# OpenEVSE_PLUS_v5.net
KiCad netlist of a schematic drawn in EAGLE
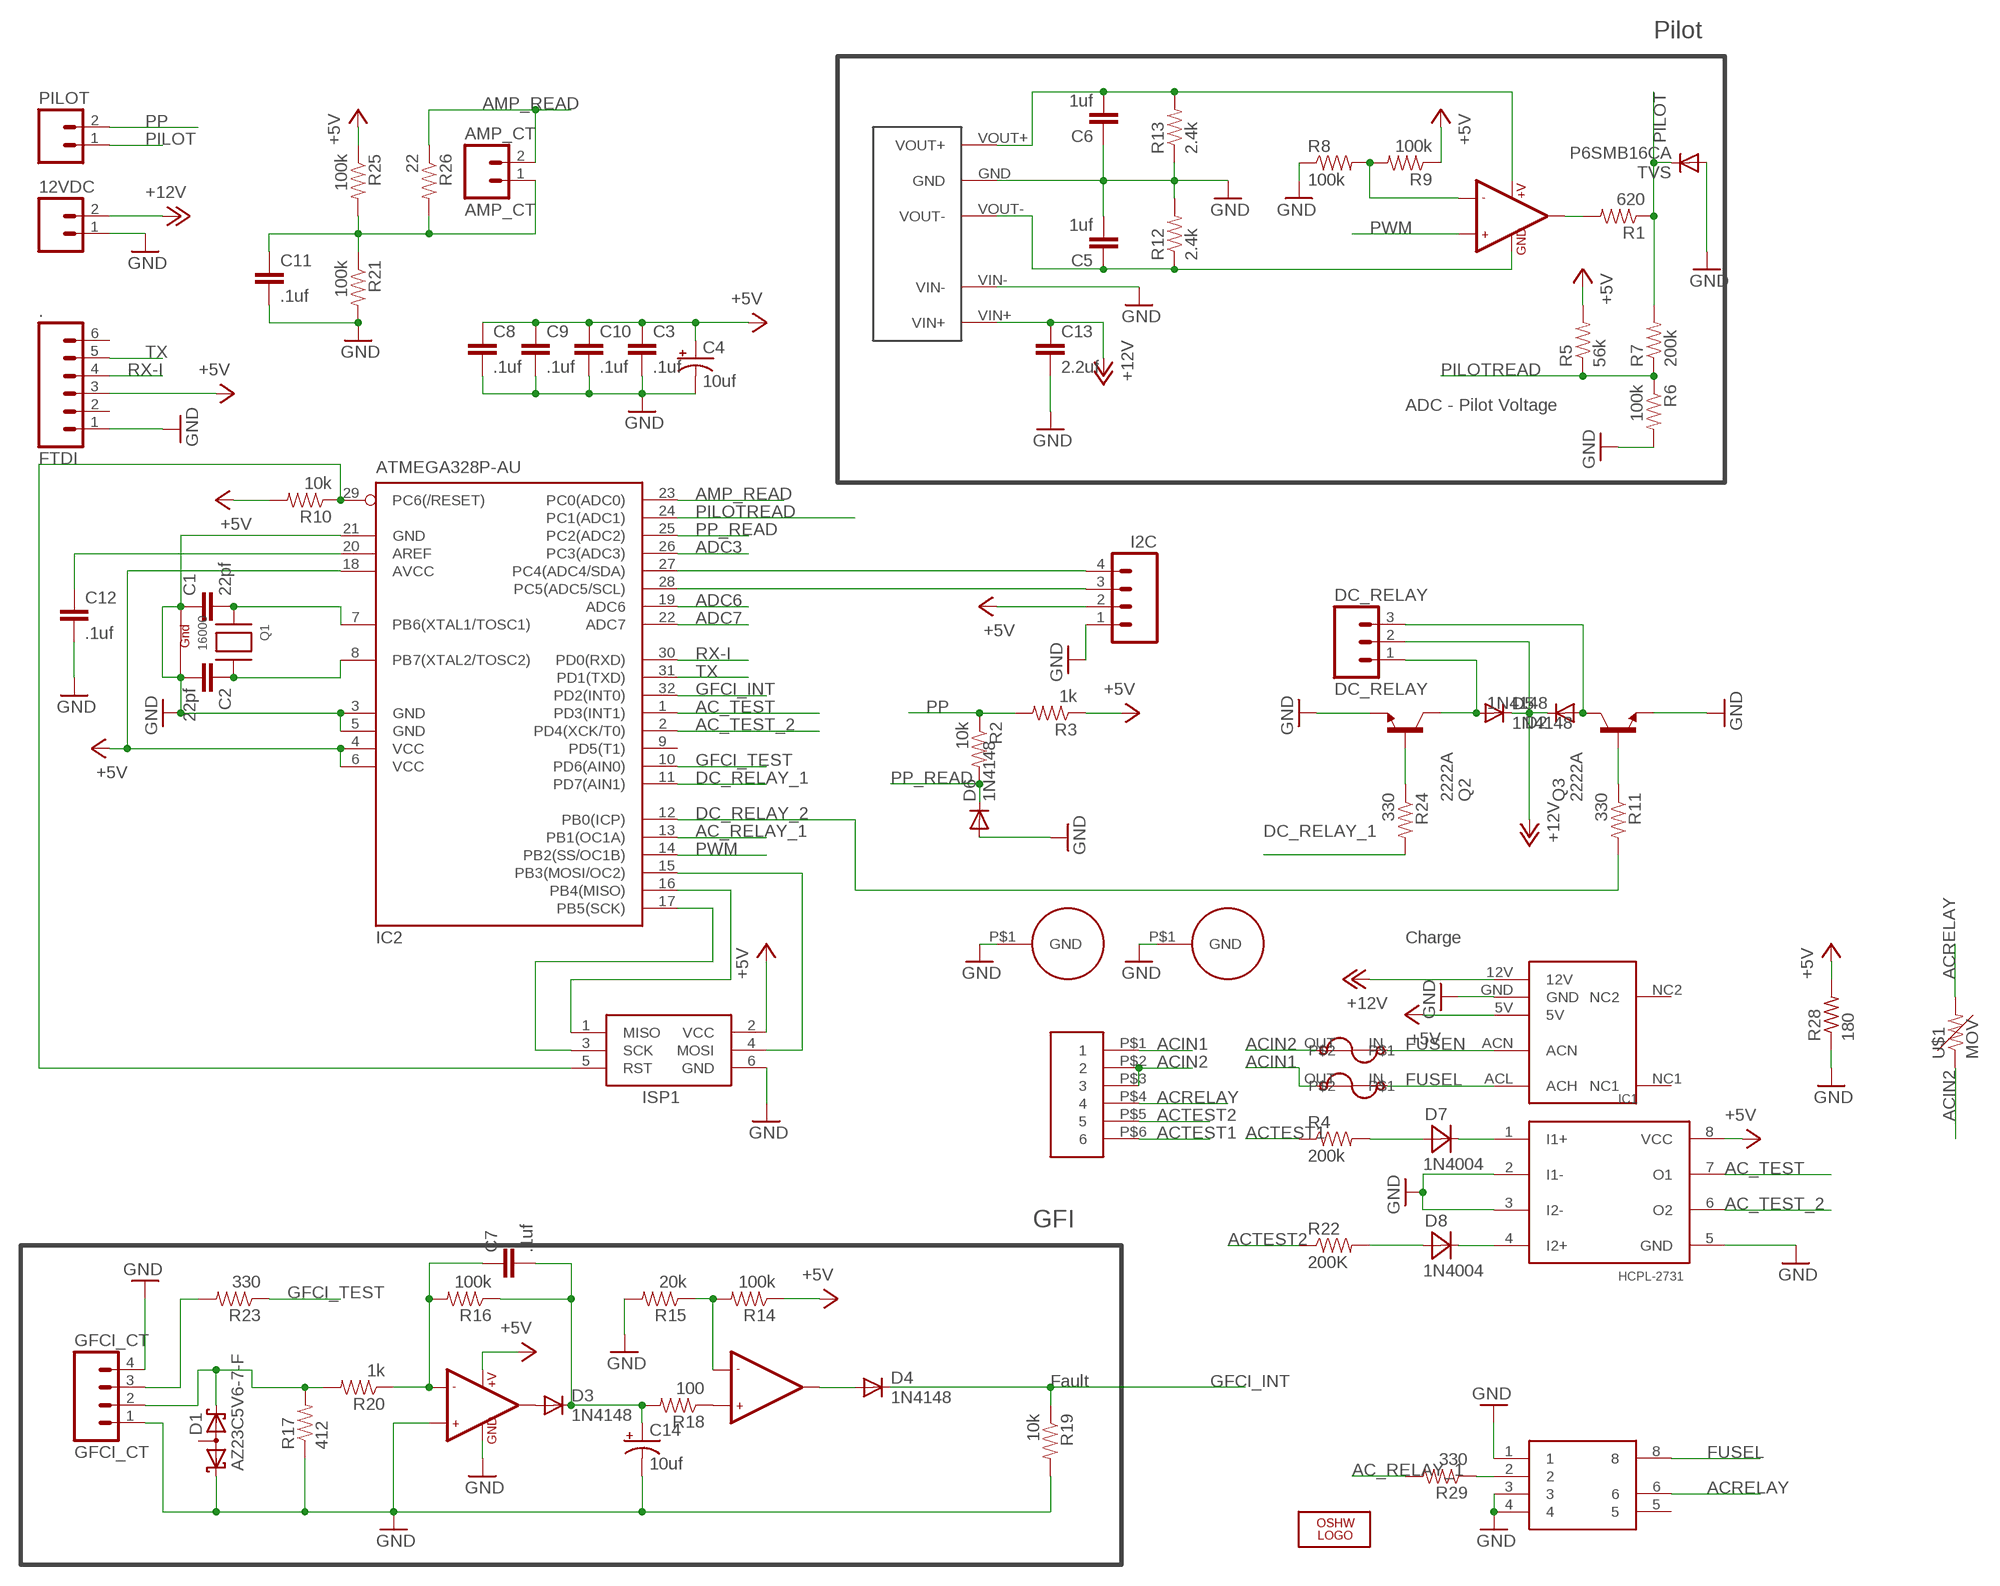
[diagram p0: schematic, sheet 1]

(export (version "E")
  (design (tool "Eeschema 10.0.6"))
  (components
    (comp (ref ".")
      (value "FTDI")
      (footprint "eagle-import:1X06_LOCK")
      (libsource (lib "eagle-import") (part "M06LOCK"))
    )
    (comp (ref "12VDC")
      (value "M023.5MM")
      (footprint "eagle-import:SCREWTERMINAL-3.5MM-2")
      (libsource (lib "eagle-import") (part "M023.5MM"))
    )
    (comp (ref "AC")
      (value "JST-VH-6")
      (footprint "eagle-import:JST-VH-6")
      (libsource (lib "eagle-import") (part "JST-VH-6"))
    )
    (comp (ref "AMP_CT")
      (value "AMP_CT")
      (footprint "eagle-import:MOLEX_2")
      (libsource (lib "eagle-import") (part "MOLEX_2"))
    )
    (comp (ref "C1")
      (value "22pf")
      (footprint "eagle-import:0805")
      (libsource (lib "eagle-import") (part "CAP0805"))
    )
    (comp (ref "C2")
      (value "22pf")
      (footprint "eagle-import:0805")
      (libsource (lib "eagle-import") (part "CAP0805"))
    )
    (comp (ref "C3")
      (value ".1uf")
      (footprint "eagle-import:0805")
      (libsource (lib "eagle-import") (part "CAP0805"))
    )
    (comp (ref "C4")
      (value "10uf")
      (footprint "eagle-import:EIA3216")
      (libsource (lib "eagle-import") (part "CAP_POL1206"))
    )
    (comp (ref "C5")
      (value "1uf")
      (footprint "eagle-import:0805")
      (libsource (lib "eagle-import") (part "CAP0805"))
    )
    (comp (ref "C6")
      (value "1uf")
      (footprint "eagle-import:0805")
      (libsource (lib "eagle-import") (part "CAP0805"))
    )
    (comp (ref "C7")
      (value ".1uf")
      (footprint "eagle-import:0805")
      (libsource (lib "eagle-import") (part "CAP0805"))
    )
    (comp (ref "C8")
      (value ".1uf")
      (footprint "eagle-import:0805")
      (libsource (lib "eagle-import") (part "CAP0805"))
    )
    (comp (ref "C9")
      (value ".1uf")
      (footprint "eagle-import:0805")
      (libsource (lib "eagle-import") (part "CAP0805"))
    )
    (comp (ref "C10")
      (value ".1uf")
      (footprint "eagle-import:0805")
      (libsource (lib "eagle-import") (part "CAP0805"))
    )
    (comp (ref "C11")
      (value ".1uf")
      (footprint "eagle-import:0805")
      (libsource (lib "eagle-import") (part "CAP0805"))
    )
    (comp (ref "C12")
      (value ".1uf")
      (footprint "eagle-import:0805")
      (libsource (lib "eagle-import") (part "CAP0805"))
    )
    (comp (ref "C13")
      (value "2.2uf")
      (footprint "eagle-import:0805")
      (libsource (lib "eagle-import") (part "CAP0805"))
    )
    (comp (ref "C14")
      (value "10uf")
      (footprint "eagle-import:EIA3216")
      (libsource (lib "eagle-import") (part "CAP_POL1206"))
    )
    (comp (ref "D1")
      (value "AZ23C5V6-7-F")
      (footprint "eagle-import:SOT23")
      (libsource (lib "eagle-import") (part "BAS40-06"))
    )
    (comp (ref "D2")
      (value "1N4148")
      (footprint "eagle-import:SOD123")
      (libsource (lib "eagle-import") (part "DIODE-SOD123"))
    )
    (comp (ref "D3")
      (value "1N4148")
      (footprint "eagle-import:SOD123")
      (libsource (lib "eagle-import") (part "DIODE-SOD123"))
    )
    (comp (ref "D4")
      (value "1N4148")
      (footprint "eagle-import:SOD123")
      (libsource (lib "eagle-import") (part "DIODE-SOD123"))
    )
    (comp (ref "D5")
      (value "1N4148")
      (footprint "eagle-import:SOD123")
      (libsource (lib "eagle-import") (part "DIODE-SOD123"))
    )
    (comp (ref "D6")
      (value "1N4148")
      (footprint "eagle-import:SOD123")
      (libsource (lib "eagle-import") (part "DIODE-SOD123"))
    )
    (comp (ref "D7")
      (value "1N4004")
      (footprint "eagle-import:SMA")
      (libsource (lib "eagle-import") (part "MBRA340T3"))
    )
    (comp (ref "D8")
      (value "1N4004")
      (footprint "eagle-import:SMA")
      (libsource (lib "eagle-import") (part "MBRA340T3"))
    )
    (comp (ref "DCDC")
      (value "MD112D-12E")
      (footprint "eagle-import:DCDC_SIP")
      (libsource (lib "eagle-import") (part "DCDC_SIP"))
    )
    (comp (ref "DC_RELAY")
      (value "DC_RELAY")
      (footprint "eagle-import:MOLEX_3")
      (libsource (lib "eagle-import") (part "MOLEX_3"))
    )
    (comp (ref "F1")
      (value "BEL1AFUSE")
      (footprint "eagle-import:BELFUSE1A")
      (libsource (lib "eagle-import") (part "BEL1AFUSE"))
    )
    (comp (ref "F2")
      (value "BEL1AFUSE")
      (footprint "eagle-import:BELFUSE1A")
      (libsource (lib "eagle-import") (part "BEL1AFUSE"))
    )
    (comp (ref "GFCI_CT")
      (value "GFCI_CT")
      (footprint "eagle-import:GFCI_4")
      (libsource (lib "eagle-import") (part "GFCI_4"))
    )
    (comp (ref "I2C")
      (value "M04LOCK")
      (footprint "eagle-import:1X04_LOCK")
      (libsource (lib "eagle-import") (part "M04LOCK"))
    )
    (comp (ref "IC1")
      (value "HCPL-2731")
      (footprint "eagle-import:DIP08")
      (libsource (lib "eagle-import") (part "HCPL-2731"))
    )
    (comp (ref "IC2")
      (value "ATMEGA328P-AU")
      (footprint "eagle-import:TQFP32-08")
      (fields (field (name "MPN") "ATMEGA8-16AU"))
      (libsource (lib "eagle-import") (part "MEGA8-AI"))
    )
    (comp (ref "IC3")
      (value "LM358")
      (footprint "eagle-import:SO08")
      (libsource (lib "eagle-import") (part "LMV358"))
    )
    (comp (ref "IC4")
      (value "LF353")
      (footprint "eagle-import:SO08")
      (libsource (lib "eagle-import") (part "LMV358"))
    )
    (comp (ref "IC5")
      (value "AQH1213")
      (footprint "eagle-import:DIP7")
      (libsource (lib "eagle-import") (part "AQH1213"))
    )
    (comp (ref "ISP1")
      (value "AVRISP-6")
      (footprint "eagle-import:AVRISP")
      (libsource (lib "eagle-import") (part "AVRISP-6"))
    )
    (comp (ref "LOGO1")
      (value "OSHW_LOGO_8MILX0150-NT")
      (footprint "eagle-import:OSHW_8X150_NOTEXT")
      (libsource (lib "eagle-import") (part "OSHW_LOGO_8MILX0150-NT"))
    )
    (comp (ref "PILOT")
      (value "M023.5MM")
      (footprint "eagle-import:SCREWTERMINAL-3.5MM-2")
      (libsource (lib "eagle-import") (part "M023.5MM"))
    )
    (comp (ref "PS1")
      (value "MPM-04E-1205")
      (footprint "eagle-import:MPM-04E-1205")
      (libsource (lib "eagle-import") (part "MPM-04E-1205"))
    )
    (comp (ref "Q1")
      (value "16000")
      (footprint "eagle-import:NX3225")
      (libsource (lib "eagle-import") (part "XTAL-4-3225"))
    )
    (comp (ref "Q2")
      (value "2222A")
      (footprint "eagle-import:SOT23")
      (libsource (lib "eagle-import") (part "BCX70SMD"))
    )
    (comp (ref "Q3")
      (value "2222A")
      (footprint "eagle-import:SOT23")
      (libsource (lib "eagle-import") (part "BCX70SMD"))
    )
    (comp (ref "R1")
      (value "620")
      (footprint "eagle-import:0805")
      (libsource (lib "eagle-import") (part "RESISTOR0805-RES"))
    )
    (comp (ref "R2")
      (value "10k")
      (footprint "eagle-import:0805")
      (libsource (lib "eagle-import") (part "RESISTOR0805-RES"))
    )
    (comp (ref "R3")
      (value "1k")
      (footprint "eagle-import:0805")
      (libsource (lib "eagle-import") (part "RESISTOR0805-RES"))
    )
    (comp (ref "R4")
      (value "200k")
      (footprint "eagle-import:AXIAL-0.4")
      (libsource (lib "eagle-import") (part "RESISTORPTH-1/4W"))
    )
    (comp (ref "R5")
      (value "56k")
      (footprint "eagle-import:0805")
      (libsource (lib "eagle-import") (part "RESISTOR0805-RES"))
    )
    (comp (ref "R6")
      (value "100k")
      (footprint "eagle-import:0805")
      (libsource (lib "eagle-import") (part "RESISTOR0805-RES"))
    )
    (comp (ref "R7")
      (value "200k")
      (footprint "eagle-import:0805")
      (libsource (lib "eagle-import") (part "RESISTOR0805-RES"))
    )
    (comp (ref "R8")
      (value "100k")
      (footprint "eagle-import:0805")
      (libsource (lib "eagle-import") (part "RESISTOR0805-RES"))
    )
    (comp (ref "R9")
      (value "100k")
      (footprint "eagle-import:0805")
      (libsource (lib "eagle-import") (part "RESISTOR0805-RES"))
    )
    (comp (ref "R10")
      (value "10k")
      (footprint "eagle-import:0805")
      (libsource (lib "eagle-import") (part "RESISTOR0805-RES"))
    )
    (comp (ref "R11")
      (value "330")
      (footprint "eagle-import:0805")
      (libsource (lib "eagle-import") (part "RESISTOR0805-RES"))
    )
    (comp (ref "R12")
      (value "2.4k")
      (footprint "eagle-import:0805")
      (libsource (lib "eagle-import") (part "RESISTOR0805-RES"))
    )
    (comp (ref "R13")
      (value "2.4k")
      (footprint "eagle-import:0805")
      (libsource (lib "eagle-import") (part "RESISTOR0805-RES"))
    )
    (comp (ref "R14")
      (value "100k")
      (footprint "eagle-import:0805")
      (libsource (lib "eagle-import") (part "RESISTOR0805-RES"))
    )
    (comp (ref "R15")
      (value "20k")
      (footprint "eagle-import:0805")
      (libsource (lib "eagle-import") (part "RESISTOR0805-RES"))
    )
    (comp (ref "R16")
      (value "100k")
      (footprint "eagle-import:0805")
      (libsource (lib "eagle-import") (part "RESISTOR0805-RES"))
    )
    (comp (ref "R17")
      (value "412")
      (footprint "eagle-import:0805")
      (libsource (lib "eagle-import") (part "RESISTOR0805-RES"))
    )
    (comp (ref "R18")
      (value "100")
      (footprint "eagle-import:0805")
      (libsource (lib "eagle-import") (part "RESISTOR0805-RES"))
    )
    (comp (ref "R19")
      (value "10k")
      (footprint "eagle-import:0805")
      (libsource (lib "eagle-import") (part "RESISTOR0805-RES"))
    )
    (comp (ref "R20")
      (value "1k")
      (footprint "eagle-import:0805")
      (libsource (lib "eagle-import") (part "RESISTOR0805-RES"))
    )
    (comp (ref "R21")
      (value "100k")
      (footprint "eagle-import:0805")
      (libsource (lib "eagle-import") (part "RESISTOR0805-RES"))
    )
    (comp (ref "R22")
      (value "200K")
      (footprint "eagle-import:AXIAL-0.4")
      (libsource (lib "eagle-import") (part "RESISTORPTH-1/4W"))
    )
    (comp (ref "R23")
      (value "330")
      (footprint "eagle-import:0805")
      (libsource (lib "eagle-import") (part "RESISTOR0805-RES"))
    )
    (comp (ref "R24")
      (value "330")
      (footprint "eagle-import:0805")
      (libsource (lib "eagle-import") (part "RESISTOR0805-RES"))
    )
    (comp (ref "R25")
      (value "100k")
      (footprint "eagle-import:0805")
      (libsource (lib "eagle-import") (part "RESISTOR0805-RES"))
    )
    (comp (ref "R26")
      (value "22")
      (footprint "eagle-import:0805")
      (libsource (lib "eagle-import") (part "RESISTOR0805-RES"))
    )
    (comp (ref "R28")
      (value "180")
      (footprint "eagle-import:R1206")
      (libsource (lib "eagle-import") (part "R-US_R1206"))
    )
    (comp (ref "R29")
      (value "330")
      (footprint "eagle-import:0805")
      (libsource (lib "eagle-import") (part "RESISTOR0805-RES"))
    )
    (comp (ref "TVS")
      (value "P6SMB16CA")
      (footprint "eagle-import:SMB")
      (libsource (lib "eagle-import") (part "DIODE-SMB"))
    )
    (comp (ref "U$1")
      (value "MOV")
      (footprint "eagle-import:MOV")
      (libsource (lib "eagle-import") (part "MOV"))
    )
    (comp (ref "U$3")
      (value "HOLE")
      (footprint "eagle-import:HOLE")
      (libsource (lib "eagle-import") (part "HOLE"))
    )
    (comp (ref "U$4")
      (value "HOLE")
      (footprint "eagle-import:HOLE")
      (libsource (lib "eagle-import") (part "HOLE"))
    )
  )
  (nets
    (net (code "1") (name "+5V") (class "Default")
      (node (ref ".") (pin "3") (pinfunction "3_3") (pintype "passive"))
      (node (ref "C10") (pin "1") (pinfunction "1_1") (pintype "passive"))
      (node (ref "C3") (pin "1") (pinfunction "1_1") (pintype "passive"))
      (node (ref "C4") (pin "A") (pinfunction "+_A") (pintype "passive"))
      (node (ref "C8") (pin "1") (pinfunction "1_1") (pintype "passive"))
      (node (ref "C9") (pin "1") (pinfunction "1_1") (pintype "passive"))
      (node (ref "I2C") (pin "2") (pinfunction "2_2") (pintype "passive"))
      (node (ref "IC1") (pin "8") (pinfunction "VCC_8") (pintype "bidirectional"))
      (node (ref "IC2") (pin "18") (pinfunction "AVCC_18") (pintype "power_in"))
      (node (ref "IC2") (pin "4") (pinfunction "VCC_4") (pintype "power_in"))
      (node (ref "IC2") (pin "6") (pinfunction "VCC_6") (pintype "power_in"))
      (node (ref "IC3") (pin "8") (pinfunction "+V_8") (pintype "power_in"))
      (node (ref "ISP1") (pin "2") (pinfunction "VCC_2") (pintype "power_in"))
      (node (ref "PS1") (pin "5V") (pinfunction "5V_5V") (pintype "bidirectional"))
      (node (ref "R10") (pin "2") (pinfunction "2_2") (pintype "passive"))
      (node (ref "R14") (pin "1") (pinfunction "1_1") (pintype "passive"))
      (node (ref "R25") (pin "1") (pinfunction "1_1") (pintype "passive"))
      (node (ref "R28") (pin "2") (pinfunction "2_2") (pintype "passive"))
      (node (ref "R3") (pin "1") (pinfunction "1_1") (pintype "passive"))
      (node (ref "R5") (pin "2") (pinfunction "2_2") (pintype "passive"))
      (node (ref "R9") (pin "1") (pinfunction "1_1") (pintype "passive"))
    )
    (net (code "2") (name "+12V") (class "Default")
      (node (ref "12VDC") (pin "2") (pinfunction "2_2") (pintype "passive"))
      (node (ref "C13") (pin "1") (pinfunction "1_1") (pintype "passive"))
      (node (ref "D2") (pin "C") (pinfunction "C_C") (pintype "passive"))
      (node (ref "D5") (pin "C") (pinfunction "C_C") (pintype "passive"))
      (node (ref "DCDC") (pin "VIN+") (pinfunction "VIN+_VIN+") (pintype "bidirectional"))
      (node (ref "DC_RELAY") (pin "2") (pinfunction "2_2") (pintype "passive"))
      (node (ref "PS1") (pin "12V") (pinfunction "12V_12V") (pintype "bidirectional"))
    )
    (net (code "3") (name "/ACIN1") (class "Default")
      (node (ref "AC") (pin "P$1") (pinfunction "1_P$1") (pintype "bidirectional"))
      (node (ref "F2") (pin "OUT") (pinfunction "P$1_OUT") (pintype "bidirectional"))
    )
    (net (code "4") (name "/ACIN2") (class "Default")
      (node (ref "AC") (pin "P$2") (pinfunction "2_P$2") (pintype "bidirectional"))
      (node (ref "AC") (pin "P$3") (pinfunction "3_P$3") (pintype "bidirectional"))
      (node (ref "F1") (pin "OUT") (pinfunction "P$1_OUT") (pintype "bidirectional"))
      (node (ref "U$1") (pin "P$1") (pinfunction "1_P$1") (pintype "passive"))
    )
    (net (code "5") (name "/ACRELAY") (class "Default")
      (node (ref "AC") (pin "P$4") (pinfunction "4_P$4") (pintype "bidirectional"))
      (node (ref "IC5") (pin "6") (pinfunction "6_6") (pintype "bidirectional"))
      (node (ref "U$1") (pin "P$2") (pinfunction "2_P$2") (pintype "passive"))
    )
    (net (code "6") (name "/ACTEST1") (class "Default")
      (node (ref "AC") (pin "P$6") (pinfunction "6_P$6") (pintype "bidirectional"))
      (node (ref "R4") (pin "P$1") (pinfunction "1_P$1") (pintype "passive"))
    )
    (net (code "7") (name "/ACTEST2") (class "Default")
      (node (ref "AC") (pin "P$5") (pinfunction "5_P$5") (pintype "bidirectional"))
      (node (ref "R22") (pin "P$1") (pinfunction "1_P$1") (pintype "passive"))
    )
    (net (code "8") (name "/AC_RELAY_1") (class "Default")
      (node (ref "IC2") (pin "13") (pinfunction "PB1(OC1A)_13") (pintype "bidirectional"))
      (node (ref "R29") (pin "2") (pinfunction "2_2") (pintype "passive"))
    )
    (net (code "9") (name "/AC_TEST") (class "Default")
      (node (ref "IC1") (pin "7") (pinfunction "O1_7") (pintype "bidirectional"))
      (node (ref "IC2") (pin "1") (pinfunction "PD3(INT1)_1") (pintype "bidirectional"))
    )
    (net (code "10") (name "/AC_TEST_2") (class "Default")
      (node (ref "IC1") (pin "6") (pinfunction "O2_6") (pintype "bidirectional"))
      (node (ref "IC2") (pin "2") (pinfunction "PD4(XCK/T0)_2") (pintype "bidirectional"))
    )
    (net (code "11") (name "/ADC3") (class "Default")
      (node (ref "IC2") (pin "26") (pinfunction "PC3(ADC3)_26") (pintype "bidirectional"))
    )
    (net (code "12") (name "/ADC6") (class "Default")
      (node (ref "IC2") (pin "19") (pinfunction "ADC6_19") (pintype "bidirectional"))
    )
    (net (code "13") (name "/ADC7") (class "Default")
      (node (ref "IC2") (pin "22") (pinfunction "ADC7_22") (pintype "bidirectional"))
    )
    (net (code "14") (name "/AMP_READ") (class "Default")
      (node (ref "AMP_CT") (pin "2") (pinfunction "2_2") (pintype "passive"))
      (node (ref "IC2") (pin "23") (pinfunction "PC0(ADC0)_23") (pintype "bidirectional"))
      (node (ref "R26") (pin "1") (pinfunction "1_1") (pintype "passive"))
    )
    (net (code "15") (name "/DC_RELAY_1") (class "Default")
      (node (ref "IC2") (pin "11") (pinfunction "PD7(AIN1)_11") (pintype "bidirectional"))
      (node (ref "R24") (pin "2") (pinfunction "2_2") (pintype "passive"))
    )
    (net (code "16") (name "/DC_RELAY_2") (class "Default")
      (node (ref "IC2") (pin "12") (pinfunction "PB0(ICP)_12") (pintype "bidirectional"))
      (node (ref "R11") (pin "2") (pinfunction "2_2") (pintype "passive"))
    )
    (net (code "17") (name "/FUSEL") (class "Default")
      (node (ref "F2") (pin "IN") (pinfunction "P$2_IN") (pintype "bidirectional"))
      (node (ref "IC5") (pin "8") (pinfunction "8_8") (pintype "bidirectional"))
      (node (ref "PS1") (pin "ACL") (pinfunction "ACH_ACL") (pintype "bidirectional"))
    )
    (net (code "18") (name "/FUSEN") (class "Default")
      (node (ref "F1") (pin "IN") (pinfunction "P$2_IN") (pintype "bidirectional"))
      (node (ref "PS1") (pin "ACN") (pinfunction "ACN_ACN") (pintype "bidirectional"))
    )
    (net (code "19") (name "/GFCI_INT") (class "Default")
      (node (ref "D4") (pin "C") (pinfunction "C_C") (pintype "passive"))
      (node (ref "IC2") (pin "32") (pinfunction "PD2(INT0)_32") (pintype "bidirectional"))
      (node (ref "R19") (pin "1") (pinfunction "1_1") (pintype "passive"))
    )
    (net (code "20") (name "/GFCI_TEST") (class "Default")
      (node (ref "IC2") (pin "10") (pinfunction "PD6(AIN0)_10") (pintype "bidirectional"))
      (node (ref "R23") (pin "1") (pinfunction "1_1") (pintype "passive"))
    )
    (net (code "21") (name "/PILOT") (class "Default")
      (node (ref "PILOT") (pin "1") (pinfunction "1_1") (pintype "passive"))
      (node (ref "R1") (pin "1") (pinfunction "1_1") (pintype "passive"))
      (node (ref "R7") (pin "2") (pinfunction "2_2") (pintype "passive"))
      (node (ref "TVS") (pin "C") (pinfunction "C_C") (pintype "passive"))
    )
    (net (code "22") (name "/PILOTREAD") (class "Default")
      (node (ref "IC2") (pin "24") (pinfunction "PC1(ADC1)_24") (pintype "bidirectional"))
      (node (ref "R5") (pin "1") (pinfunction "1_1") (pintype "passive"))
      (node (ref "R6") (pin "1") (pinfunction "1_1") (pintype "passive"))
      (node (ref "R7") (pin "1") (pinfunction "1_1") (pintype "passive"))
    )
    (net (code "23") (name "/PP") (class "Default")
      (node (ref "PILOT") (pin "2") (pinfunction "2_2") (pintype "passive"))
      (node (ref "R2") (pin "1") (pinfunction "1_1") (pintype "passive"))
      (node (ref "R3") (pin "2") (pinfunction "2_2") (pintype "passive"))
    )
    (net (code "24") (name "/PP_READ") (class "Default")
      (node (ref "D6") (pin "C") (pinfunction "C_C") (pintype "passive"))
      (node (ref "IC2") (pin "25") (pinfunction "PC2(ADC2)_25") (pintype "bidirectional"))
      (node (ref "R2") (pin "2") (pinfunction "2_2") (pintype "passive"))
    )
    (net (code "25") (name "/PWM") (class "Default")
      (node (ref "IC2") (pin "14") (pinfunction "PB2(SS/OC1B)_14") (pintype "bidirectional"))
      (node (ref "IC4") (pin "3") (pinfunction "+IN1_3") (pintype "input"))
    )
    (net (code "26") (name "/RX-I") (class "Default")
      (node (ref ".") (pin "4") (pinfunction "4_4") (pintype "passive"))
      (node (ref "IC2") (pin "30") (pinfunction "PD0(RXD)_30") (pintype "bidirectional"))
    )
    (net (code "27") (name "/TX") (class "Default")
      (node (ref ".") (pin "5") (pinfunction "5_5") (pintype "passive"))
      (node (ref "IC2") (pin "31") (pinfunction "PD1(TXD)_31") (pintype "bidirectional"))
    )
    (net (code "28") (name "GND") (class "Default")
      (node (ref ".") (pin "1") (pinfunction "1_1") (pintype "passive"))
      (node (ref "12VDC") (pin "1") (pinfunction "1_1") (pintype "passive"))
      (node (ref "C1") (pin "1") (pinfunction "1_1") (pintype "passive"))
      (node (ref "C10") (pin "2") (pinfunction "2_2") (pintype "passive"))
      (node (ref "C11") (pin "2") (pinfunction "2_2") (pintype "passive"))
      (node (ref "C12") (pin "2") (pinfunction "2_2") (pintype "passive"))
      (node (ref "C13") (pin "2") (pinfunction "2_2") (pintype "passive"))
      (node (ref "C14") (pin "C") (pinfunction "-_C") (pintype "passive"))
      (node (ref "C2") (pin "2") (pinfunction "2_2") (pintype "passive"))
      (node (ref "C3") (pin "2") (pinfunction "2_2") (pintype "passive"))
      (node (ref "C4") (pin "C") (pinfunction "-_C") (pintype "passive"))
      (node (ref "C5") (pin "2") (pinfunction "2_2") (pintype "passive"))
      (node (ref "C6") (pin "1") (pinfunction "1_1") (pintype "passive"))
      (node (ref "C8") (pin "2") (pinfunction "2_2") (pintype "passive"))
      (node (ref "C9") (pin "2") (pinfunction "2_2") (pintype "passive"))
      (node (ref "D1") (pin "1") (pinfunction "K1_1") (pintype "passive"))
      (node (ref "D6") (pin "A") (pinfunction "A_A") (pintype "passive"))
      (node (ref "DCDC") (pin "GND") (pinfunction "GND_GND") (pintype "bidirectional"))
      (node (ref "DCDC") (pin "VIN-") (pinfunction "VIN-_VIN-") (pintype "bidirectional"))
      (node (ref "GFCI_CT") (pin "1") (pinfunction "1_1") (pintype "passive"))
      (node (ref "GFCI_CT") (pin "4") (pinfunction "4_4") (pintype "passive"))
      (node (ref "I2C") (pin "1") (pinfunction "1_1") (pintype "passive"))
      (node (ref "IC1") (pin "2") (pinfunction "I1-_2") (pintype "bidirectional"))
      (node (ref "IC1") (pin "3") (pinfunction "I2-_3") (pintype "bidirectional"))
      (node (ref "IC1") (pin "5") (pinfunction "GND_5") (pintype "bidirectional"))
      (node (ref "IC2") (pin "21") (pinfunction "GND_21") (pintype "power_in"))
      (node (ref "IC2") (pin "3") (pinfunction "GND_3") (pintype "power_in"))
      (node (ref "IC2") (pin "5") (pinfunction "GND_5") (pintype "power_in"))
      (node (ref "IC3") (pin "3") (pinfunction "+IN1_3") (pintype "input"))
      (node (ref "IC3") (pin "4") (pinfunction "GND_4") (pintype "power_in"))
      (node (ref "IC5") (pin "1") (pinfunction "1_1") (pintype "bidirectional"))
      (node (ref "IC5") (pin "3") (pinfunction "3_3") (pintype "bidirectional"))
      (node (ref "IC5") (pin "4") (pinfunction "4_4") (pintype "bidirectional"))
      (node (ref "ISP1") (pin "6") (pinfunction "GND_6") (pintype "power_in"))
      (node (ref "PS1") (pin "GND") (pinfunction "GND_GND") (pintype "bidirectional"))
      (node (ref "Q1") (pin "1") (pinfunction "G1_1") (pintype "power_in"))
      (node (ref "Q1") (pin "3") (pinfunction "G2_3") (pintype "power_in"))
      (node (ref "Q2") (pin "2") (pinfunction "E_2") (pintype "passive"))
      (node (ref "Q3") (pin "2") (pinfunction "E_2") (pintype "passive"))
      (node (ref "R12") (pin "2") (pinfunction "2_2") (pintype "passive"))
      (node (ref "R13") (pin "1") (pinfunction "1_1") (pintype "passive"))
      (node (ref "R15") (pin "2") (pinfunction "2_2") (pintype "passive"))
      (node (ref "R17") (pin "1") (pinfunction "1_1") (pintype "passive"))
      (node (ref "R19") (pin "2") (pinfunction "2_2") (pintype "passive"))
      (node (ref "R21") (pin "2") (pinfunction "2_2") (pintype "passive"))
      (node (ref "R28") (pin "1") (pinfunction "1_1") (pintype "passive"))
      (node (ref "R6") (pin "2") (pinfunction "2_2") (pintype "passive"))
      (node (ref "R8") (pin "1") (pinfunction "1_1") (pintype "passive"))
      (node (ref "TVS") (pin "A") (pinfunction "A_A") (pintype "passive"))
      (node (ref "U$3") (pin "P$1") (pinfunction "GND_P$1") (pintype "bidirectional"))
      (node (ref "U$4") (pin "P$1") (pinfunction "GND_P$1") (pintype "bidirectional"))
    )
    (net (code "29") (name "Net-(AMP_CT-Pad1)") (class "Default")
      (node (ref "AMP_CT") (pin "1") (pinfunction "1_1") (pintype "passive"))
      (node (ref "C11") (pin "1") (pinfunction "1_1") (pintype "passive"))
      (node (ref "R21") (pin "1") (pinfunction "1_1") (pintype "passive"))
      (node (ref "R25") (pin "2") (pinfunction "2_2") (pintype "passive"))
      (node (ref "R26") (pin "2") (pinfunction "2_2") (pintype "passive"))
    )
    (net (code "30") (name "Net-(C14-+)") (class "Default")
      (node (ref "C14") (pin "A") (pinfunction "+_A") (pintype "passive"))
      (node (ref "C7") (pin "2") (pinfunction "2_2") (pintype "passive"))
      (node (ref "D3") (pin "C") (pinfunction "C_C") (pintype "passive"))
      (node (ref "R16") (pin "1") (pinfunction "1_1") (pintype "passive"))
      (node (ref "R18") (pin "2") (pinfunction "2_2") (pintype "passive"))
    )
    (net (code "31") (name "Net-(D1-K2)") (class "Default")
      (node (ref "D1") (pin "2") (pinfunction "K2_2") (pintype "passive"))
      (node (ref "GFCI_CT") (pin "2") (pinfunction "2_2") (pintype "passive"))
      (node (ref "R17") (pin "2") (pinfunction "2_2") (pintype "passive"))
      (node (ref "R20") (pin "2") (pinfunction "2_2") (pintype "passive"))
    )
    (net (code "32") (name "Net-(GFCI_CT-Pad3)") (class "Default")
      (node (ref "GFCI_CT") (pin "3") (pinfunction "3_3") (pintype "passive"))
      (node (ref "R23") (pin "2") (pinfunction "2_2") (pintype "passive"))
    )
    (net (code "33") (name "Net-(IC1-I1+)") (class "Default")
      (node (ref "D7") (pin "C") (pinfunction "C_C") (pintype "passive"))
      (node (ref "IC1") (pin "1") (pinfunction "I1+_1") (pintype "bidirectional"))
    )
    (net (code "34") (name "Net-(IC1-I2+)") (class "Default")
      (node (ref "D8") (pin "C") (pinfunction "C_C") (pintype "passive"))
      (node (ref "IC1") (pin "4") (pinfunction "I2+_4") (pintype "bidirectional"))
    )
    (net (code "35") (name "Net-(IC2-AREF)") (class "Default")
      (node (ref "C12") (pin "1") (pinfunction "1_1") (pintype "passive"))
      (node (ref "IC2") (pin "20") (pinfunction "AREF_20") (pintype "passive"))
    )
    (net (code "36") (name "Net-(IC2-PB3(MOSI{slash}OC2))") (class "Default")
      (node (ref "IC2") (pin "15") (pinfunction "PB3(MOSI/OC2)_15") (pintype "bidirectional"))
      (node (ref "ISP1") (pin "4") (pinfunction "MOSI_4") (pintype "output"))
    )
    (net (code "37") (name "Net-(IC2-PB4(MISO))") (class "Default")
      (node (ref "IC2") (pin "16") (pinfunction "PB4(MISO)_16") (pintype "bidirectional"))
      (node (ref "ISP1") (pin "1") (pinfunction "MISO_1") (pintype "input"))
    )
    (net (code "38") (name "Net-(IC2-PB5(SCK))") (class "Default")
      (node (ref "IC2") (pin "17") (pinfunction "PB5(SCK)_17") (pintype "bidirectional"))
      (node (ref "ISP1") (pin "3") (pinfunction "SCK_3") (pintype "output"))
    )
    (net (code "39") (name "Net-(IC2-PB6(XTAL1{slash}TOSC1))") (class "Default")
      (node (ref "C1") (pin "2") (pinfunction "2_2") (pintype "passive"))
      (node (ref "IC2") (pin "7") (pinfunction "PB6(XTAL1/TOSC1)_7") (pintype "bidirectional"))
      (node (ref "Q1") (pin "2") (pinfunction "X1_2") (pintype "bidirectional"))
    )
    (net (code "40") (name "Net-(IC2-PB7(XTAL2{slash}TOSC2))") (class "Default")
      (node (ref "C2") (pin "1") (pinfunction "1_1") (pintype "passive"))
      (node (ref "IC2") (pin "8") (pinfunction "PB7(XTAL2/TOSC2)_8") (pintype "bidirectional"))
      (node (ref "Q1") (pin "4") (pinfunction "X2_4") (pintype "bidirectional"))
    )
    (net (code "41") (name "Net-(IC2-PC4(ADC4{slash}SDA))") (class "Default")
      (node (ref "I2C") (pin "4") (pinfunction "4_4") (pintype "passive"))
      (node (ref "IC2") (pin "27") (pinfunction "PC4(ADC4/SDA)_27") (pintype "bidirectional"))
    )
    (net (code "42") (name "Net-(IC2-PC5(ADC5{slash}SCL))") (class "Default")
      (node (ref "I2C") (pin "3") (pinfunction "3_3") (pintype "passive"))
      (node (ref "IC2") (pin "28") (pinfunction "PC5(ADC5/SCL)_28") (pintype "bidirectional"))
    )
    (net (code "43") (name "Net-(IC2-PC6({slash}RESET))") (class "Default")
      (node (ref "IC2") (pin "29") (pinfunction "PC6(/RESET)_29") (pintype "bidirectional"))
      (node (ref "ISP1") (pin "5") (pinfunction "RST_5") (pintype "output"))
      (node (ref "R10") (pin "1") (pinfunction "1_1") (pintype "passive"))
    )
    (net (code "44") (name "Net-(IC3A--IN1)") (class "Default")
      (node (ref "C7") (pin "1") (pinfunction "1_1") (pintype "passive"))
      (node (ref "IC3") (pin "2") (pinfunction "-IN1_2") (pintype "input"))
      (node (ref "R16") (pin "2") (pinfunction "2_2") (pintype "passive"))
      (node (ref "R20") (pin "1") (pinfunction "1_1") (pintype "passive"))
    )
    (net (code "45") (name "Net-(IC3A-OUT1)") (class "Default")
      (node (ref "D3") (pin "A") (pinfunction "A_A") (pintype "passive"))
      (node (ref "IC3") (pin "1") (pinfunction "OUT1_1") (pintype "output"))
    )
    (net (code "46") (name "Net-(IC3B-+IN2)") (class "Default")
      (node (ref "IC3") (pin "5") (pinfunction "+IN2_5") (pintype "input"))
      (node (ref "R18") (pin "1") (pinfunction "1_1") (pintype "passive"))
    )
    (net (code "47") (name "Net-(IC3B--IN2)") (class "Default")
      (node (ref "IC3") (pin "6") (pinfunction "-IN2_6") (pintype "input"))
      (node (ref "R14") (pin "2") (pinfunction "2_2") (pintype "passive"))
      (node (ref "R15") (pin "1") (pinfunction "1_1") (pintype "passive"))
    )
    (net (code "48") (name "Net-(IC3B-OUT2)") (class "Default")
      (node (ref "D4") (pin "A") (pinfunction "A_A") (pintype "passive"))
      (node (ref "IC3") (pin "7") (pinfunction "OUT2_7") (pintype "output"))
    )
    (net (code "49") (name "Net-(IC4A-+V)") (class "Default")
      (node (ref "C6") (pin "2") (pinfunction "2_2") (pintype "passive"))
      (node (ref "DCDC") (pin "VOUT+") (pinfunction "VOUT+_VOUT+") (pintype "bidirectional"))
      (node (ref "IC4") (pin "8") (pinfunction "+V_8") (pintype "power_in"))
      (node (ref "R13") (pin "2") (pinfunction "2_2") (pintype "passive"))
    )
    (net (code "50") (name "Net-(IC4A--IN1)") (class "Default")
      (node (ref "IC4") (pin "2") (pinfunction "-IN1_2") (pintype "input"))
      (node (ref "R8") (pin "2") (pinfunction "2_2") (pintype "passive"))
      (node (ref "R9") (pin "2") (pinfunction "2_2") (pintype "passive"))
    )
    (net (code "51") (name "Net-(IC4A-GND)") (class "Default")
      (node (ref "C5") (pin "1") (pinfunction "1_1") (pintype "passive"))
      (node (ref "DCDC") (pin "VOUT-") (pinfunction "VOUT-_VOUT-") (pintype "bidirectional"))
      (node (ref "IC4") (pin "4") (pinfunction "GND_4") (pintype "power_in"))
      (node (ref "R12") (pin "1") (pinfunction "1_1") (pintype "passive"))
    )
    (net (code "52") (name "Net-(IC4A-OUT1)") (class "Default")
      (node (ref "IC4") (pin "1") (pinfunction "OUT1_1") (pintype "output"))
      (node (ref "R1") (pin "2") (pinfunction "2_2") (pintype "passive"))
    )
    (net (code "53") (name "Net-(IC5-Pad2)") (class "Default")
      (node (ref "IC5") (pin "2") (pinfunction "2_2") (pintype "bidirectional"))
      (node (ref "R29") (pin "1") (pinfunction "1_1") (pintype "passive"))
    )
    (net (code "54") (name "Net-(Q2-B)") (class "Default")
      (node (ref "Q2") (pin "1") (pinfunction "B_1") (pintype "passive"))
      (node (ref "R24") (pin "1") (pinfunction "1_1") (pintype "passive"))
    )
    (net (code "55") (name "Net-(Q2-C)") (class "Default")
      (node (ref "D5") (pin "A") (pinfunction "A_A") (pintype "passive"))
      (node (ref "DC_RELAY") (pin "1") (pinfunction "1_1") (pintype "passive"))
      (node (ref "Q2") (pin "3") (pinfunction "C_3") (pintype "passive"))
    )
    (net (code "56") (name "Net-(Q3-B)") (class "Default")
      (node (ref "Q3") (pin "1") (pinfunction "B_1") (pintype "passive"))
      (node (ref "R11") (pin "1") (pinfunction "1_1") (pintype "passive"))
    )
    (net (code "57") (name "Net-(Q3-C)") (class "Default")
      (node (ref "D2") (pin "A") (pinfunction "A_A") (pintype "passive"))
      (node (ref "DC_RELAY") (pin "3") (pinfunction "3_3") (pintype "passive"))
      (node (ref "Q3") (pin "3") (pinfunction "C_3") (pintype "passive"))
    )
    (net (code "58") (name "Net-(R4-2)") (class "Default")
      (node (ref "D7") (pin "A") (pinfunction "A_A") (pintype "passive"))
      (node (ref "R4") (pin "P$2") (pinfunction "2_P$2") (pintype "passive"))
    )
    (net (code "59") (name "Net-(R22-2)") (class "Default")
      (node (ref "D8") (pin "A") (pinfunction "A_A") (pintype "passive"))
      (node (ref "R22") (pin "P$2") (pinfunction "2_P$2") (pintype "passive"))
    )
    (net (code "60") (name "unconnected-(.-Pad2)") (class "Default")
      (node (ref ".") (pin "2") (pinfunction "2_2") (pintype "passive"))
    )
    (net (code "61") (name "unconnected-(.-Pad6)") (class "Default")
      (node (ref ".") (pin "6") (pinfunction "6_6") (pintype "passive"))
    )
    (net (code "62") (name "unconnected-(D1-AA-Pad3)") (class "Default")
      (node (ref "D1") (pin "3") (pinfunction "AA_3") (pintype "passive"))
    )
    (net (code "63") (name "unconnected-(IC2-PD5(T1)-Pad9)") (class "Default")
      (node (ref "IC2") (pin "9") (pinfunction "PD5(T1)_9") (pintype "bidirectional"))
    )
    (net (code "64") (name "unconnected-(IC5-Pad5)") (class "Default")
      (node (ref "IC5") (pin "5") (pinfunction "5_5") (pintype "bidirectional"))
    )
    (net (code "65") (name "unconnected-(PS1-PadNC1)") (class "Default")
      (node (ref "PS1") (pin "NC1") (pinfunction "NC1_NC1") (pintype "bidirectional"))
    )
    (net (code "66") (name "unconnected-(PS1-PadNC2)") (class "Default")
      (node (ref "PS1") (pin "NC2") (pinfunction "NC2_NC2") (pintype "bidirectional"))
    )
  )
)
